# Fihl54-xtalOven.net
KiCad netlist of a schematic drawn in EAGLE
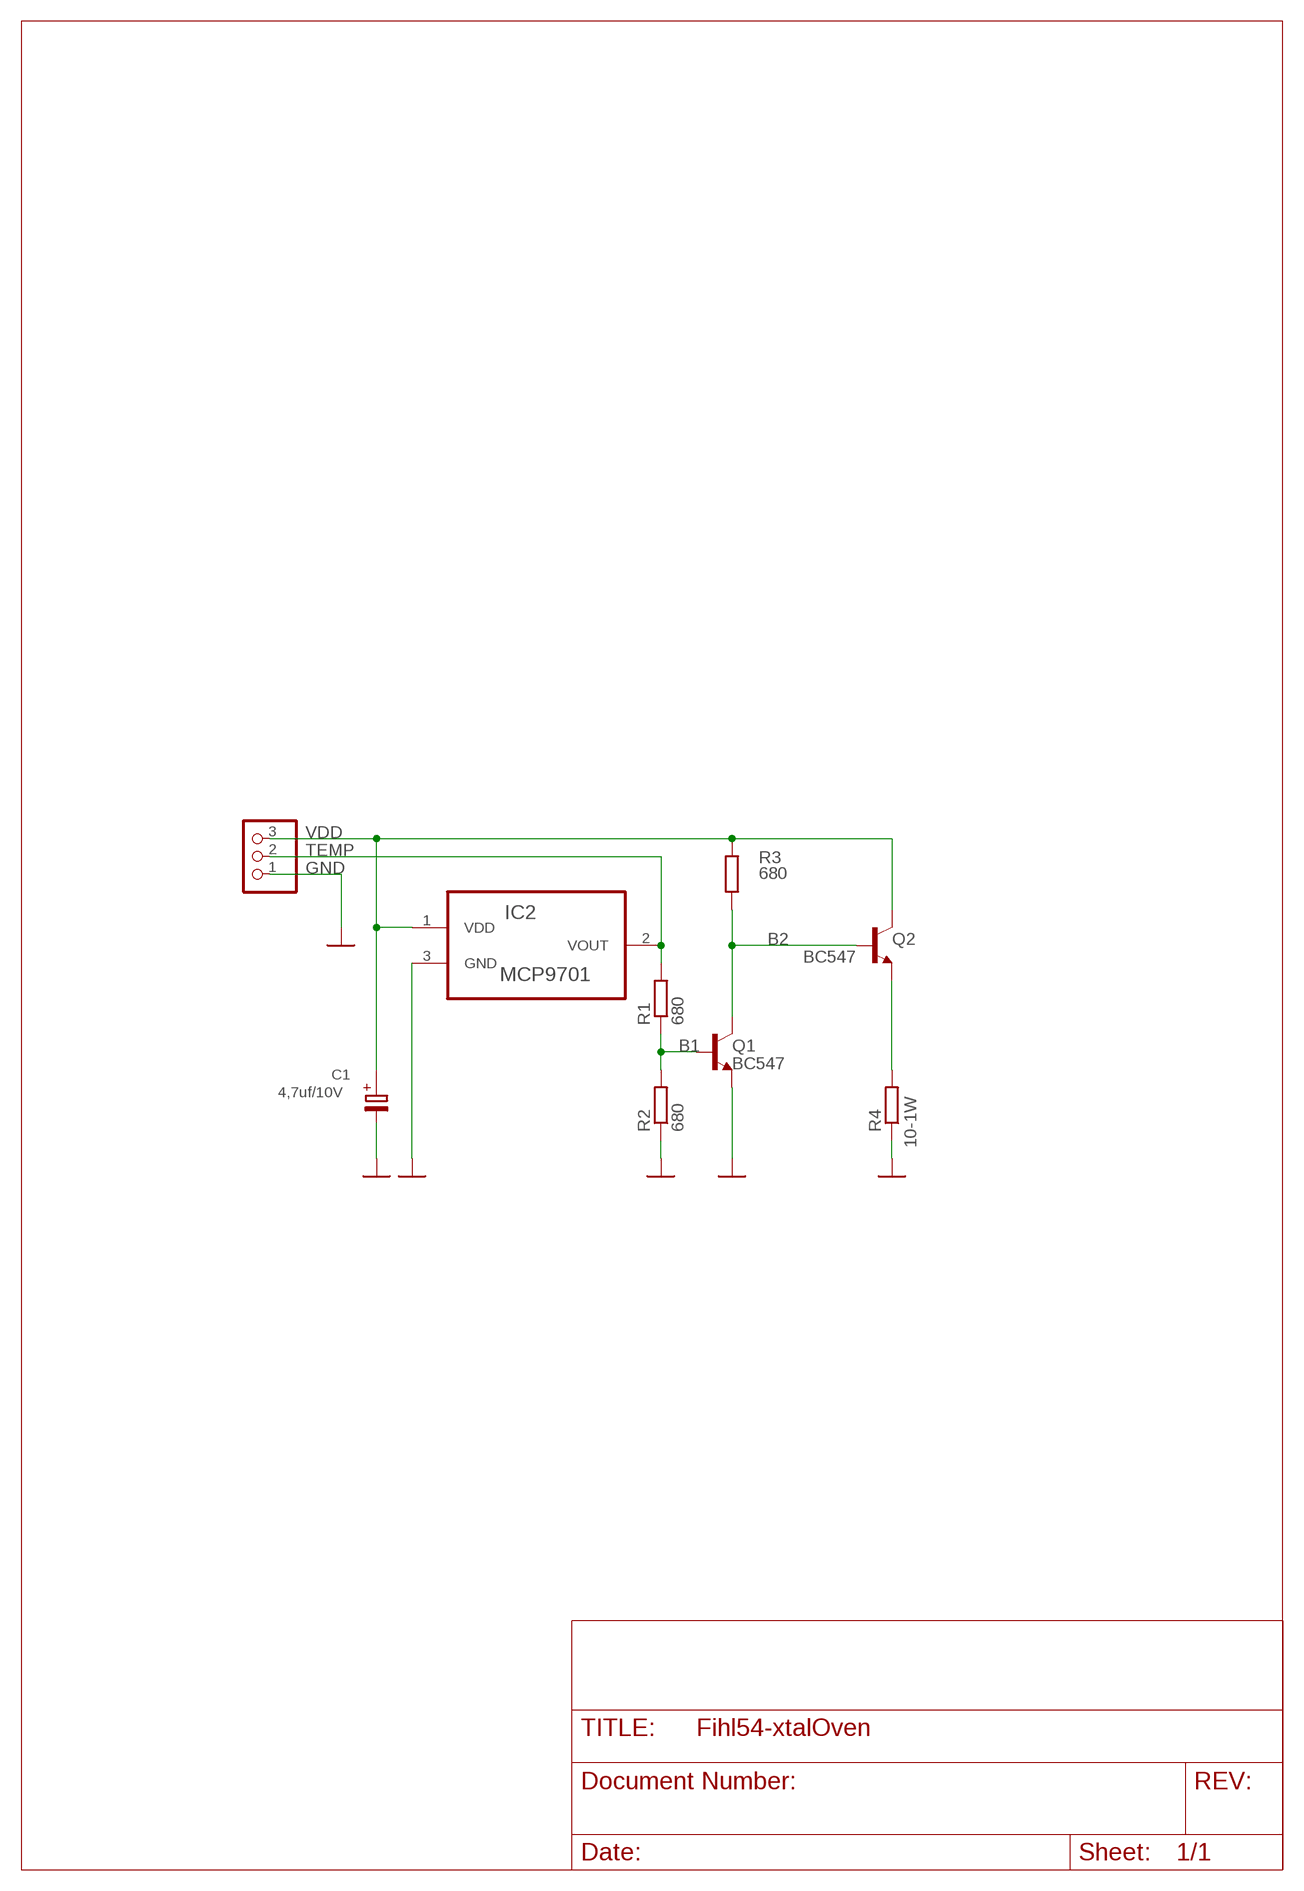
[diagram p0: schematic, sheet 1]

(export (version "E")
  (design (tool "Eeschema 10.0.6"))
  (components
    (comp (ref "C1")
      (value "4,7uf/10V")
      (footprint "eagle-import:E2,5-5")
      (libsource (lib "eagle-import") (part "E2,5-5"))
    )
    (comp (ref "IC2")
      (value "MCP9701")
      (footprint "eagle-import:TO127P254X533-3")
      (fields (field (name "MF") "Microchip") (field (name "MP") "MCP9701-E/TO"))
      (libsource (lib "eagle-import") (part "MCP9701-E/TO"))
    )
    (comp (ref "JP1")
      (value "jp1")
      (footprint "eagle-import:1X03")
      (libsource (lib "eagle-import") (part "PINHD-1X3"))
    )
    (comp (ref "Q1")
      (value "BC547")
      (footprint "eagle-import:TO92")
      (libsource (lib "eagle-import") (part "BC547"))
    )
    (comp (ref "Q2")
      (value "BC547")
      (footprint "eagle-import:TO92")
      (libsource (lib "eagle-import") (part "BC547"))
    )
    (comp (ref "R1")
      (value "680")
      (footprint "eagle-import:0309V")
      (libsource (lib "eagle-import") (part "R-EU_0309/V"))
    )
    (comp (ref "R2")
      (value "680")
      (footprint "eagle-import:0309V")
      (libsource (lib "eagle-import") (part "R-EU_0309/V"))
    )
    (comp (ref "R3")
      (value "680")
      (footprint "eagle-import:0309V")
      (libsource (lib "eagle-import") (part "R-EU_0309/V"))
    )
    (comp (ref "R4")
      (value "10-1W")
      (footprint "eagle-import:0309V")
      (libsource (lib "eagle-import") (part "R-EU_0309/V"))
    )
  )
  (nets
    (net (code "1") (name "/B1") (class "Default")
      (node (ref "Q1") (pin "2") (pinfunction "B_2") (pintype "passive"))
      (node (ref "R1") (pin "1") (pinfunction "1_1") (pintype "passive"))
      (node (ref "R2") (pin "2") (pinfunction "2_2") (pintype "passive"))
    )
    (net (code "2") (name "/B2") (class "Default")
      (node (ref "Q1") (pin "3") (pinfunction "C_3") (pintype "passive"))
      (node (ref "Q2") (pin "2") (pinfunction "B_2") (pintype "passive"))
      (node (ref "R3") (pin "1") (pinfunction "1_1") (pintype "passive"))
    )
    (net (code "3") (name "/TEMP") (class "Default")
      (node (ref "IC2") (pin "2") (pinfunction "VOUT_2") (pintype "output"))
      (node (ref "JP1") (pin "2") (pinfunction "2_2") (pintype "passive"))
      (node (ref "R1") (pin "2") (pinfunction "2_2") (pintype "passive"))
    )
    (net (code "4") (name "/VDD") (class "Default")
      (node (ref "C1") (pin "+") (pinfunction "+_+") (pintype "passive"))
      (node (ref "IC2") (pin "1") (pinfunction "VDD_1") (pintype "power_in"))
      (node (ref "JP1") (pin "3") (pinfunction "3_3") (pintype "passive"))
      (node (ref "Q2") (pin "3") (pinfunction "C_3") (pintype "passive"))
      (node (ref "R3") (pin "2") (pinfunction "2_2") (pintype "passive"))
    )
    (net (code "5") (name "GND") (class "Default")
      (node (ref "C1") (pin "-") (pinfunction "-_-") (pintype "passive"))
      (node (ref "IC2") (pin "3") (pinfunction "GND_3") (pintype "passive"))
      (node (ref "JP1") (pin "1") (pinfunction "1_1") (pintype "passive"))
      (node (ref "Q1") (pin "1") (pinfunction "E_1") (pintype "passive"))
      (node (ref "R2") (pin "1") (pinfunction "1_1") (pintype "passive"))
      (node (ref "R4") (pin "1") (pinfunction "1_1") (pintype "passive"))
    )
    (net (code "6") (name "Net-(Q2-E)") (class "Default")
      (node (ref "Q2") (pin "1") (pinfunction "E_1") (pintype "passive"))
      (node (ref "R4") (pin "2") (pinfunction "2_2") (pintype "passive"))
    )
  )
)
